# Peripherals.net
KiCad netlist of a schematic drawn in Altium Designer
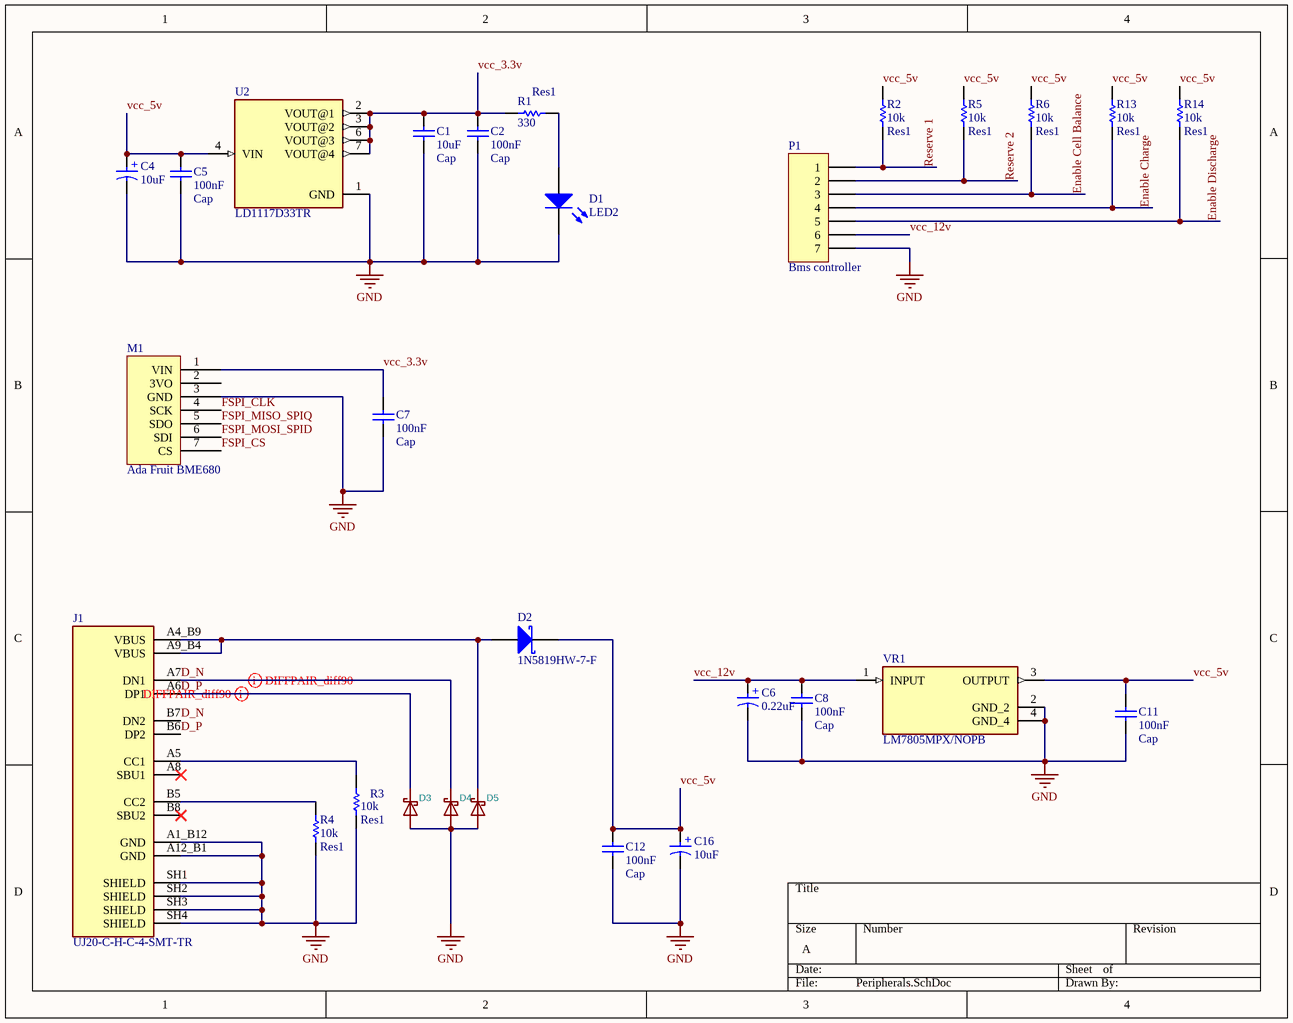
[diagram p0: Peripherals.SchDoc]

(export (version "E")
  (design (tool "Eeschema 10.0.6"))
  (components
    (comp (ref "C1")
      (value "Cap")
      (footprint "6-0805_L")
      (description "Capacitor")
      (fields (field (name "ALTIUM_VALUE") "10uF") (field (name "PUBLISHER") "Altium Limited"))
      (libsource (lib "Miscellaneous Devices") (part "Cap"))
    )
    (comp (ref "C2")
      (value "Cap")
      (footprint "6-0805_L")
      (description "Capacitor")
      (fields (field (name "ALTIUM_VALUE") "100nF") (field (name "PUBLISHER") "Altium Limited"))
      (libsource (lib "Miscellaneous Devices") (part "Cap"))
    )
    (comp (ref "C4")
      (value "10uF")
      (footprint "WCAP-ASLL_D6.3H5.5")
      (description "WCAP-ASLL Aluminum Electrolytic Capacitor, V-Chip, SMT, D6.3 x H5.5mm, 10uF, 50V")
      (fields
        (field (name "MANUFACTURER PART NUMBER") "865060643005")
        (field (name "MANUFACTURER") "Wurth Elektronik")
      )
      (libsource (lib "865060140001_Altium_WCAP-ASLL_rev24b") (part "865060643005"))
    )
    (comp (ref "C5")
      (value "Cap")
      (footprint "6-0805_L")
      (description "Capacitor")
      (fields (field (name "ALTIUM_VALUE") "100nF") (field (name "PUBLISHER") "Altium Limited"))
      (libsource (lib "Miscellaneous Devices") (part "Cap"))
    )
    (comp (ref "C6")
      (value "0.22uF")
      (footprint "WCAP-ASLL_D6.3H5.5")
      (description "WCAP-ASLL Aluminum Electrolytic Capacitor, V-Chip, SMT, D6.3 x H5.5mm, 10uF, 50V")
      (fields
        (field (name "MANUFACTURER PART NUMBER") "865060643005")
        (field (name "MANUFACTURER") "Wurth Elektronik")
      )
      (libsource (lib "865060140001_Altium_WCAP-ASLL_rev24b") (part "865060643005"))
    )
    (comp (ref "C7")
      (value "Cap")
      (footprint "6-0805_L")
      (description "Capacitor")
      (fields (field (name "ALTIUM_VALUE") "100nF") (field (name "PUBLISHER") "Altium Limited"))
      (libsource (lib "Miscellaneous Devices") (part "Cap"))
    )
    (comp (ref "C8")
      (value "Cap")
      (footprint "6-0805_L")
      (description "Capacitor")
      (fields (field (name "ALTIUM_VALUE") "100nF") (field (name "PUBLISHER") "Altium Limited"))
      (libsource (lib "Miscellaneous Devices") (part "Cap"))
    )
    (comp (ref "C11")
      (value "Cap")
      (footprint "6-0805_L")
      (description "Capacitor")
      (fields (field (name "ALTIUM_VALUE") "100nF") (field (name "PUBLISHER") "Altium Limited"))
      (libsource (lib "Miscellaneous Devices") (part "Cap"))
    )
    (comp (ref "C12")
      (value "Cap")
      (footprint "6-0805_L")
      (description "Capacitor")
      (fields (field (name "ALTIUM_VALUE") "100nF") (field (name "PUBLISHER") "Altium Limited"))
      (libsource (lib "Miscellaneous Devices") (part "Cap"))
    )
    (comp (ref "C16")
      (value "10uF")
      (footprint "WCAP-ASLL_D6.3H5.5")
      (description "WCAP-ASLL Aluminum Electrolytic Capacitor, V-Chip, SMT, D6.3 x H5.5mm, 10uF, 50V")
      (fields
        (field (name "MANUFACTURER PART NUMBER") "865060643005")
        (field (name "MANUFACTURER") "Wurth Elektronik")
      )
      (libsource (lib "865060140001_Altium_WCAP-ASLL_rev24b") (part "865060643005"))
    )
    (comp (ref "D1")
      (value "LED2")
      (footprint "6-0805_N")
      (description "Typical RED, GREEN, YELLOW, AMBER GaAs LED")
      (fields (field (name "PUBLISHER") "Altium Limited"))
      (libsource (lib "Miscellaneous Devices") (part "LED2"))
    )
    (comp (ref "D2")
      (value "1N5819HW-7-F")
      (footprint "SMB")
      (description "Schottky Diode")
      (fields (field (name "PUBLISHER") "Altium Limited"))
      (libsource (lib "Miscellaneous Devices") (part "D Schottky"))
    )
    (comp (ref "D3")
      (value "Schottky-Diode")
      (footprint "SOD-523")
      (libsource (lib "ESDB5V0WT") (part "Schottky-Diode"))
    )
    (comp (ref "D4")
      (value "Schottky-Diode")
      (footprint "SOD-523")
      (libsource (lib "ESDB5V0WT") (part "Schottky-Diode"))
    )
    (comp (ref "D5")
      (value "Schottky-Diode")
      (footprint "SOD-523")
      (libsource (lib "ESDB5V0WT") (part "Schottky-Diode"))
    )
    (comp (ref "J1")
      (value "UJ20-C-H-C-4-SMT-TR")
      (footprint "CUI_UJ20-C-H-C-4-SMT-TR")
      (libsource (lib "UJ20-C-H-C-4-SMT-TR") (part "UJ20-C-H-C-4-SMT-TR"))
    )
    (comp (ref "M1")
      (value "Ada Fruit BME680")
      (footprint "Ada Fruit BME680")
      (description "BME680 sensor module")
      (libsource (lib "esp32-s3-can-interface") (part "Ada Fruit BME680"))
    )
    (comp (ref "P1")
      (value "Bms controller")
      (footprint "HDR1X7")
      (description "Header, 7-Pin")
      (fields (field (name "PUBLISHER") "Altium Limited"))
      (libsource (lib "Miscellaneous Connectors") (part "Header 7"))
    )
    (comp (ref "R1")
      (value "Res1")
      (footprint "6-0805_N")
      (description "Resistor")
      (fields (field (name "ALTIUM_VALUE") "330") (field (name "PUBLISHER") "Altium Limited"))
      (libsource (lib "Miscellaneous Devices") (part "Res1"))
    )
    (comp (ref "R2")
      (value "Res1")
      (footprint "6-0805_N")
      (description "Resistor")
      (fields (field (name "ALTIUM_VALUE") "10k") (field (name "PUBLISHER") "Altium Limited"))
      (libsource (lib "Miscellaneous Devices") (part "Res1"))
    )
    (comp (ref "R3")
      (value "Res1")
      (footprint "6-0805_N")
      (description "Resistor")
      (fields (field (name "ALTIUM_VALUE") "10k") (field (name "PUBLISHER") "Altium Limited"))
      (libsource (lib "Miscellaneous Devices") (part "Res1"))
    )
    (comp (ref "R4")
      (value "Res1")
      (footprint "6-0805_N")
      (description "Resistor")
      (fields (field (name "ALTIUM_VALUE") "10k") (field (name "PUBLISHER") "Altium Limited"))
      (libsource (lib "Miscellaneous Devices") (part "Res1"))
    )
    (comp (ref "R5")
      (value "Res1")
      (footprint "6-0805_N")
      (description "Resistor")
      (fields (field (name "ALTIUM_VALUE") "10k") (field (name "PUBLISHER") "Altium Limited"))
      (libsource (lib "Miscellaneous Devices") (part "Res1"))
    )
    (comp (ref "R6")
      (value "Res1")
      (footprint "6-0805_N")
      (description "Resistor")
      (fields (field (name "ALTIUM_VALUE") "10k") (field (name "PUBLISHER") "Altium Limited"))
      (libsource (lib "Miscellaneous Devices") (part "Res1"))
    )
    (comp (ref "R13")
      (value "Res1")
      (footprint "6-0805_N")
      (description "Resistor")
      (fields (field (name "ALTIUM_VALUE") "10k") (field (name "PUBLISHER") "Altium Limited"))
      (libsource (lib "Miscellaneous Devices") (part "Res1"))
    )
    (comp (ref "R14")
      (value "Res1")
      (footprint "6-0805_N")
      (description "Resistor")
      (fields (field (name "ALTIUM_VALUE") "10k") (field (name "PUBLISHER") "Altium Limited"))
      (libsource (lib "Miscellaneous Devices") (part "Res1"))
    )
    (comp (ref "U2")
      (value "LD1117D33TR")
      (footprint "SOIC127P600X175-8N")
      (description "Linear Voltage Regulator IC Positive Fixed 1 Output 800mA 8-SOIC")
      (fields (field (name "MF") "STMicroelectronics"))
      (libsource (lib "LD1117D33TR") (part "LD1117D33TR"))
    )
    (comp (ref "VR1")
      (value "LM7805MPX/NOPB")
      (footprint "VREG_LM7805MPX/NOPB")
      (description "1.5-A, 30-V, linear voltage regulator 4-SOT-223 0 to 125")
      (libsource (lib "LM7805MPX_NOPB") (part "LM7805MPX/NOPB"))
    )
  )
  (nets
    (net (code "1") (name "/D_N") (class "Default")
      (node (ref "D4") (pin "K") (pinfunction "K_K") (pintype "passive"))
      (node (ref "J1") (pin "A7") (pinfunction "DN1_A7") (pintype "passive"))
      (node (ref "J1") (pin "B7") (pinfunction "DN2_B7") (pintype "passive"))
    )
    (net (code "2") (name "/D_P") (class "Default")
      (node (ref "D3") (pin "K") (pinfunction "K_K") (pintype "passive"))
      (node (ref "J1") (pin "A6") (pinfunction "DP1_A6") (pintype "passive"))
      (node (ref "J1") (pin "B6") (pinfunction "DP2_B6") (pintype "passive"))
    )
    (net (code "3") (name "/Enable Cell Balance") (class "Default")
      (node (ref "P1") (pin "3") (pinfunction "3_3") (pintype "passive"))
      (node (ref "R6") (pin "1") (pinfunction "1_1") (pintype "passive"))
    )
    (net (code "4") (name "/Enable Charge") (class "Default")
      (node (ref "P1") (pin "4") (pinfunction "4_4") (pintype "passive"))
      (node (ref "R13") (pin "1") (pinfunction "1_1") (pintype "passive"))
    )
    (net (code "5") (name "/Enable Discharge") (class "Default")
      (node (ref "P1") (pin "5") (pinfunction "5_5") (pintype "passive"))
      (node (ref "R14") (pin "1") (pinfunction "1_1") (pintype "passive"))
    )
    (net (code "6") (name "/FSPI_CLK") (class "Default")
      (node (ref "M1") (pin "4") (pinfunction "SCK_4") (pintype "passive"))
    )
    (net (code "7") (name "/FSPI_CS") (class "Default")
      (node (ref "M1") (pin "7") (pinfunction "CS_7") (pintype "passive"))
    )
    (net (code "8") (name "/FSPI_MISO_SPIQ") (class "Default")
      (node (ref "M1") (pin "5") (pinfunction "SDO_5") (pintype "passive"))
    )
    (net (code "9") (name "/FSPI_MOSI_SPID") (class "Default")
      (node (ref "M1") (pin "6") (pinfunction "SDI_6") (pintype "passive"))
    )
    (net (code "10") (name "/Reserve 1") (class "Default")
      (node (ref "P1") (pin "1") (pinfunction "1_1") (pintype "passive"))
      (node (ref "R2") (pin "1") (pinfunction "1_1") (pintype "passive"))
    )
    (net (code "11") (name "/Reserve 2") (class "Default")
      (node (ref "P1") (pin "2") (pinfunction "2_2") (pintype "passive"))
      (node (ref "R5") (pin "1") (pinfunction "1_1") (pintype "passive"))
    )
    (net (code "12") (name "/vcc_3.3v") (class "Default")
      (node (ref "C1") (pin "2") (pinfunction "2_2") (pintype "passive"))
      (node (ref "C2") (pin "2") (pinfunction "2_2") (pintype "passive"))
      (node (ref "C7") (pin "2") (pinfunction "2_2") (pintype "passive"))
      (node (ref "M1") (pin "1") (pinfunction "VIN_1") (pintype "passive"))
      (node (ref "R1") (pin "1") (pinfunction "1_1") (pintype "passive"))
      (node (ref "U2") (pin "2") (pinfunction "VOUT@1_2") (pintype "output"))
      (node (ref "U2") (pin "3") (pinfunction "VOUT@2_3") (pintype "output"))
      (node (ref "U2") (pin "6") (pinfunction "VOUT@3_6") (pintype "output"))
      (node (ref "U2") (pin "7") (pinfunction "VOUT@4_7") (pintype "output"))
    )
    (net (code "13") (name "/vcc_5v") (class "Default")
      (node (ref "C11") (pin "2") (pinfunction "2_2") (pintype "passive"))
      (node (ref "C12") (pin "2") (pinfunction "2_2") (pintype "passive"))
      (node (ref "C16") (pin "1") (pinfunction "P_1") (pintype "passive"))
      (node (ref "C4") (pin "1") (pinfunction "P_1") (pintype "passive"))
      (node (ref "C5") (pin "2") (pinfunction "2_2") (pintype "passive"))
      (node (ref "D2") (pin "2") (pinfunction "K_2") (pintype "passive"))
      (node (ref "R13") (pin "2") (pinfunction "2_2") (pintype "passive"))
      (node (ref "R14") (pin "2") (pinfunction "2_2") (pintype "passive"))
      (node (ref "R2") (pin "2") (pinfunction "2_2") (pintype "passive"))
      (node (ref "R5") (pin "2") (pinfunction "2_2") (pintype "passive"))
      (node (ref "R6") (pin "2") (pinfunction "2_2") (pintype "passive"))
      (node (ref "U2") (pin "4") (pinfunction "VIN_4") (pintype "input"))
      (node (ref "VR1") (pin "3") (pinfunction "OUTPUT_3") (pintype "output"))
    )
    (net (code "14") (name "/vcc_12v") (class "Default")
      (node (ref "C6") (pin "1") (pinfunction "P_1") (pintype "passive"))
      (node (ref "C8") (pin "2") (pinfunction "2_2") (pintype "passive"))
      (node (ref "P1") (pin "6") (pinfunction "6_6") (pintype "passive"))
      (node (ref "VR1") (pin "1") (pinfunction "INPUT_1") (pintype "input"))
    )
    (net (code "15") (name "GND") (class "Default")
      (node (ref "C1") (pin "1") (pinfunction "1_1") (pintype "passive"))
      (node (ref "C11") (pin "1") (pinfunction "1_1") (pintype "passive"))
      (node (ref "C12") (pin "1") (pinfunction "1_1") (pintype "passive"))
      (node (ref "C16") (pin "2") (pinfunction "N_2") (pintype "passive"))
      (node (ref "C2") (pin "1") (pinfunction "1_1") (pintype "passive"))
      (node (ref "C4") (pin "2") (pinfunction "N_2") (pintype "passive"))
      (node (ref "C5") (pin "1") (pinfunction "1_1") (pintype "passive"))
      (node (ref "C6") (pin "2") (pinfunction "N_2") (pintype "passive"))
      (node (ref "C7") (pin "1") (pinfunction "1_1") (pintype "passive"))
      (node (ref "C8") (pin "1") (pinfunction "1_1") (pintype "passive"))
      (node (ref "D1") (pin "2") (pinfunction "K_2") (pintype "passive"))
      (node (ref "D3") (pin "A") (pinfunction "A_A") (pintype "passive"))
      (node (ref "D4") (pin "A") (pinfunction "A_A") (pintype "passive"))
      (node (ref "D5") (pin "A") (pinfunction "A_A") (pintype "passive"))
      (node (ref "J1") (pin "A12_B1") (pinfunction "GND_A12_B1") (pintype "passive"))
      (node (ref "J1") (pin "A1_B12") (pinfunction "GND_A1_B12") (pintype "passive"))
      (node (ref "J1") (pin "SH1") (pinfunction "SHIELD_SH1") (pintype "passive"))
      (node (ref "J1") (pin "SH2") (pinfunction "SHIELD_SH2") (pintype "passive"))
      (node (ref "J1") (pin "SH3") (pinfunction "SHIELD_SH3") (pintype "passive"))
      (node (ref "J1") (pin "SH4") (pinfunction "SHIELD_SH4") (pintype "passive"))
      (node (ref "M1") (pin "3") (pinfunction "GND_3") (pintype "passive"))
      (node (ref "P1") (pin "7") (pinfunction "7_7") (pintype "passive"))
      (node (ref "R3") (pin "1") (pinfunction "1_1") (pintype "passive"))
      (node (ref "R4") (pin "1") (pinfunction "1_1") (pintype "passive"))
      (node (ref "U2") (pin "1") (pinfunction "GND_1") (pintype "power_in"))
      (node (ref "VR1") (pin "2") (pinfunction "GND_2_2") (pintype "power_in"))
      (node (ref "VR1") (pin "4") (pinfunction "GND_4_4") (pintype "power_in"))
    )
    (net (code "16") (name "Net-(D1-A)") (class "Default")
      (node (ref "D1") (pin "1") (pinfunction "A_1") (pintype "passive"))
      (node (ref "R1") (pin "2") (pinfunction "2_2") (pintype "passive"))
    )
    (net (code "17") (name "Net-(D2-A)") (class "Default")
      (node (ref "D2") (pin "1") (pinfunction "A_1") (pintype "passive"))
      (node (ref "D5") (pin "K") (pinfunction "K_K") (pintype "passive"))
      (node (ref "J1") (pin "A4_B9") (pinfunction "VBUS_A4_B9") (pintype "passive"))
      (node (ref "J1") (pin "A9_B4") (pinfunction "VBUS_A9_B4") (pintype "passive"))
    )
    (net (code "18") (name "Net-(J1-CC1)") (class "Default")
      (node (ref "J1") (pin "A5") (pinfunction "CC1_A5") (pintype "passive"))
      (node (ref "R3") (pin "2") (pinfunction "2_2") (pintype "passive"))
    )
    (net (code "19") (name "Net-(J1-CC2)") (class "Default")
      (node (ref "J1") (pin "B5") (pinfunction "CC2_B5") (pintype "passive"))
      (node (ref "R4") (pin "2") (pinfunction "2_2") (pintype "passive"))
    )
    (net (code "20") (name "unconnected-(J1-SBU1-PadA8)") (class "Default")
      (node (ref "J1") (pin "A8") (pinfunction "SBU1_A8") (pintype "passive+no_connect"))
    )
    (net (code "21") (name "unconnected-(J1-SBU2-PadB8)") (class "Default")
      (node (ref "J1") (pin "B8") (pinfunction "SBU2_B8") (pintype "passive+no_connect"))
    )
    (net (code "22") (name "unconnected-(M1-3VO-Pad2)") (class "Default")
      (node (ref "M1") (pin "2") (pinfunction "3VO_2") (pintype "passive"))
    )
  )
)
